# WiFi.net
KiCad netlist of a schematic drawn in Altium Designer
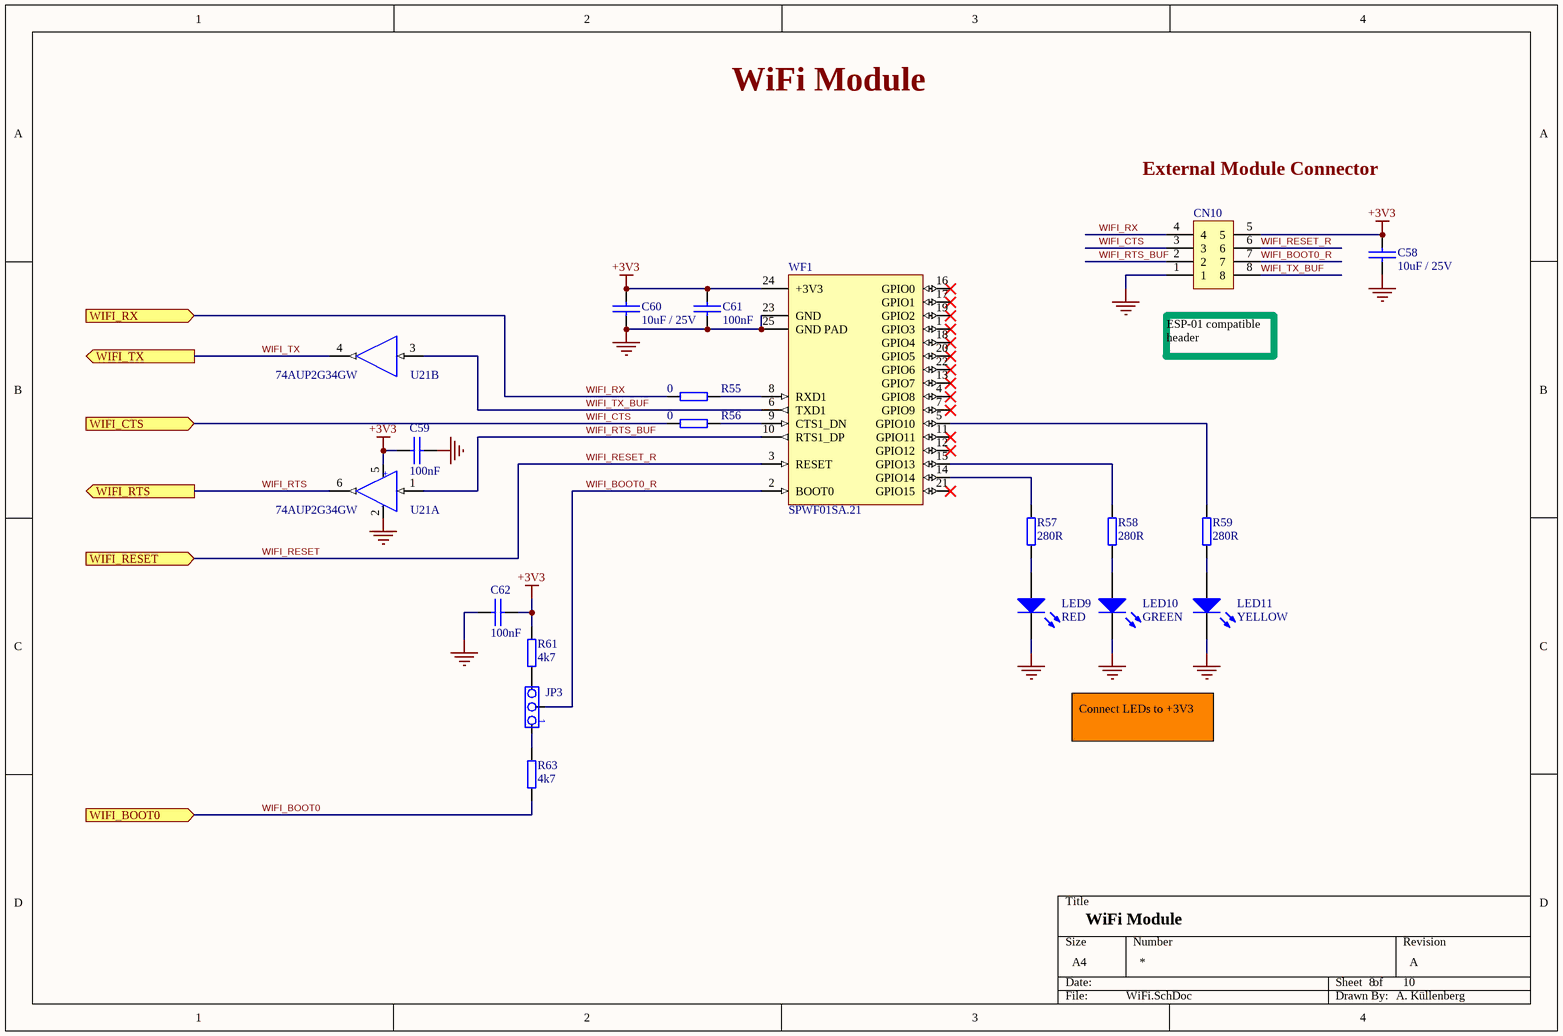
[diagram p0: WiFi.SchDoc]

(export (version "E")
  (design (tool "Eeschema 10.0.6"))
  (components
    (comp (ref "C58")
      (value "10uF / 25V")
      (footprint "C0603")
      (description "CAP CER 10UF 25V X5R 0603")
      (fields
        (field (name "PART NUMBER") "ZRB18AR61E106ME01L")
        (field (name "MANUFACTURER") "Murata Electronics North America")
      )
      (libsource (lib "AKLib") (part "CAP"))
    )
    (comp (ref "C59")
      (value "100nF")
      (footprint "C0603")
      (description "CAP CER 0.1UF 50V X7R 0603")
      (fields (field (name "PART NUMBER") "C0603C104K5RACTU") (field (name "MANUFACTURER") "Kemet"))
      (libsource (lib "AKLib") (part "CAP"))
    )
    (comp (ref "C60")
      (value "10uF / 25V")
      (footprint "C0603")
      (description "CAP CER 10UF 25V X5R 0603")
      (fields
        (field (name "PART NUMBER") "ZRB18AR61E106ME01L")
        (field (name "MANUFACTURER") "Murata Electronics North America")
      )
      (libsource (lib "AKLib") (part "CAP"))
    )
    (comp (ref "C61")
      (value "100nF")
      (footprint "C0603")
      (description "CAP CER 0.1UF 50V X7R 0603")
      (fields (field (name "PART NUMBER") "C0603C104K5RACTU") (field (name "MANUFACTURER") "Kemet"))
      (libsource (lib "AKLib") (part "CAP"))
    )
    (comp (ref "C62")
      (value "100nF")
      (footprint "C0603")
      (description "CAP CER 0.1UF 50V X7R 0603")
      (fields (field (name "PART NUMBER") "C0603C104K5RACTU") (field (name "MANUFACTURER") "Kemet"))
      (libsource (lib "AKLib") (part "CAP"))
    )
    (comp (ref "CN10")
      (value "HDR 2x4")
      (footprint "PPPC042LFBN-RC")
      (description "CONN HEADER FMAL 8PS .1\" DL GOLD")
      (fields
        (field (name "PART NUMBER") "PPPC042LFBN-RC")
        (field (name "MANUFACTURER") "Sullins Connector Solutions")
      )
      (libsource (lib "AKLib") (part "Header 2-4"))
    )
    (comp (ref "JP3")
      (value "JP")
      (footprint "HDR1x3")
      (description "CONN HEADER 3 POS 2.54")
      (fields
        (field (name "PART NUMBER") "61300311121")
        (field (name "MANUFACTURER") "Wurth Electronics Inc.")
      )
      (libsource (lib "AKLib") (part "JP1x3"))
    )
    (comp (ref "LED9")
      (value "RED")
      (footprint "LED_0603_RED")
      (description "LED RED CLEAR 0603 SMD")
      (fields (field (name "PART NUMBER") "LTST-C190KRKT") (field (name "MANUFACTURER") "Lite-On Inc."))
      (libsource (lib "AKLib") (part "LED"))
    )
    (comp (ref "LED10")
      (value "GREEN")
      (footprint "LED_0603_GREEN")
      (description "LED GREEN CLEAR 0603 SMD")
      (fields (field (name "PART NUMBER") "LTST-C190KGKT") (field (name "MANUFACTURER") "Lite-On Inc."))
      (libsource (lib "AKLib") (part "LED"))
    )
    (comp (ref "LED11")
      (value "YELLOW")
      (footprint "LED_0603_YELLOW")
      (description "LED YELLOW CLEAR 0603 SMD")
      (fields (field (name "PART NUMBER") "LTST-C190KSKT") (field (name "MANUFACTURER") "Lite-On Inc."))
      (libsource (lib "AKLib") (part "LED"))
    )
    (comp (ref "R55")
      (value "0")
      (footprint "R0603")
      (description "RES SMD 0.0OHM JUMPER 1/10W 0603")
      (fields (field (name "PART NUMBER") "RC0603JR-070RL") (field (name "MANUFACTURER") "Yageo"))
      (libsource (lib "AKLib") (part "RES"))
    )
    (comp (ref "R56")
      (value "0")
      (footprint "R0603")
      (description "RES SMD 0.0OHM JUMPER 1/10W 0603")
      (fields (field (name "PART NUMBER") "RC0603JR-070RL") (field (name "MANUFACTURER") "Yageo"))
      (libsource (lib "AKLib") (part "RES"))
    )
    (comp (ref "R57")
      (value "280R")
      (footprint "R0603")
      (description "RES SMD 280 OHM 1% 1/10W 0603")
      (fields (field (name "PART NUMBER") "RC0603FR-07280RL") (field (name "MANUFACTURER") "Yageo"))
      (libsource (lib "AKLib") (part "RES"))
    )
    (comp (ref "R58")
      (value "280R")
      (footprint "R0603")
      (description "RES SMD 280 OHM 1% 1/10W 0603")
      (fields (field (name "PART NUMBER") "RC0603FR-07280RL") (field (name "MANUFACTURER") "Yageo"))
      (libsource (lib "AKLib") (part "RES"))
    )
    (comp (ref "R59")
      (value "280R")
      (footprint "R0603")
      (description "RES SMD 280 OHM 1% 1/10W 0603")
      (fields (field (name "PART NUMBER") "RC0603FR-07280RL") (field (name "MANUFACTURER") "Yageo"))
      (libsource (lib "AKLib") (part "RES"))
    )
    (comp (ref "R61")
      (value "4k7")
      (footprint "R0603")
      (description "RES SMD 4.7K OHM 1% 1/10W 0603")
      (fields (field (name "PART NUMBER") "CRCW06034K70FKEA") (field (name "MANUFACTURER") "Vishay Dale"))
      (libsource (lib "AKLib") (part "RES"))
    )
    (comp (ref "R63")
      (value "4k7")
      (footprint "R0603")
      (description "RES SMD 4.7K OHM 1% 1/10W 0603")
      (fields (field (name "PART NUMBER") "CRCW06034K70FKEA") (field (name "MANUFACTURER") "Vishay Dale"))
      (libsource (lib "AKLib") (part "RES"))
    )
    (comp (ref "U21")
      (value "74AUP2G34GW")
      (footprint "SOT363")
      (description "IC BUFF DL LOW PWR N-INV 6TSSOP")
      (fields
        (field (name "PART NUMBER") "74AUP2G34GW,125")
        (field (name "MANUFACTURER") "Nexperia USA Inc.")
      )
      (libsource (lib "AKLib") (part "74AUP2G34GW"))
    )
    (comp (ref "WF1")
      (value "SPWF01SA.21")
      (footprint "SPWF01SA")
      (description "RF TXRX MODULE WIFI CHIP ANT")
      (fields (field (name "MANUFACTURER") "STMicroelectronics"))
      (libsource (lib "AKLib") (part "SPWF01Sx"))
    )
  )
  (nets
    (net (code "1") (name "+3V3") (class "Default")
      (node (ref "C58") (pin "2") (pinfunction "2_2") (pintype "passive"))
      (node (ref "C59") (pin "2") (pinfunction "2_2") (pintype "passive"))
      (node (ref "C60") (pin "2") (pinfunction "2_2") (pintype "passive"))
      (node (ref "C61") (pin "2") (pinfunction "2_2") (pintype "passive"))
      (node (ref "C62") (pin "1") (pinfunction "1_1") (pintype "passive"))
      (node (ref "CN10") (pin "5") (pinfunction "5_5") (pintype "passive"))
      (node (ref "R61") (pin "2") (pinfunction "2_2") (pintype "passive"))
      (node (ref "U21") (pin "5") (pinfunction "5_5") (pintype "passive"))
      (node (ref "WF1") (pin "24") (pinfunction "+3V3_24") (pintype "power_in"))
    )
    (net (code "2") (name "/WIFI_BOOT0") (class "Default")
      (node (ref "R63") (pin "1") (pinfunction "1_1") (pintype "passive"))
    )
    (net (code "3") (name "/WIFI_BOOT0_R") (class "Default")
      (node (ref "CN10") (pin "7") (pinfunction "7_7") (pintype "passive"))
      (node (ref "JP3") (pin "2") (pinfunction "2_2") (pintype "passive"))
      (node (ref "WF1") (pin "2") (pinfunction "BOOT0_2") (pintype "input"))
    )
    (net (code "4") (name "/WIFI_CTS") (class "Default")
      (node (ref "CN10") (pin "3") (pinfunction "3_3") (pintype "passive"))
      (node (ref "R56") (pin "1") (pinfunction "1_1") (pintype "passive"))
    )
    (net (code "5") (name "/WIFI_RESET") (class "Default")
      (node (ref "CN10") (pin "6") (pinfunction "6_6") (pintype "passive"))
      (node (ref "WF1") (pin "3") (pinfunction "RESET_3") (pintype "input"))
    )
    (net (code "6") (name "/WIFI_RTS") (class "Default")
      (node (ref "U21") (pin "6") (pinfunction "6_6") (pintype "output"))
    )
    (net (code "7") (name "/WIFI_RTS_BUF") (class "Default")
      (node (ref "CN10") (pin "2") (pinfunction "2_2") (pintype "passive"))
      (node (ref "U21") (pin "1") (pinfunction "1_1") (pintype "input"))
      (node (ref "WF1") (pin "10") (pinfunction "RTS1_DP_10") (pintype "output"))
    )
    (net (code "8") (name "/WIFI_RX") (class "Default")
      (node (ref "CN10") (pin "4") (pinfunction "4_4") (pintype "passive"))
      (node (ref "R55") (pin "1") (pinfunction "1_1") (pintype "passive"))
    )
    (net (code "9") (name "/WIFI_TX") (class "Default")
      (node (ref "U21") (pin "4") (pinfunction "4_4") (pintype "output"))
    )
    (net (code "10") (name "/WIFI_TX_BUF") (class "Default")
      (node (ref "CN10") (pin "8") (pinfunction "8_8") (pintype "passive"))
      (node (ref "U21") (pin "3") (pinfunction "3_3") (pintype "input"))
      (node (ref "WF1") (pin "6") (pinfunction "TXD1_6") (pintype "output"))
    )
    (net (code "11") (name "GND") (class "Default")
      (node (ref "C58") (pin "1") (pinfunction "1_1") (pintype "passive"))
      (node (ref "C59") (pin "1") (pinfunction "1_1") (pintype "passive"))
      (node (ref "C60") (pin "1") (pinfunction "1_1") (pintype "passive"))
      (node (ref "C61") (pin "1") (pinfunction "1_1") (pintype "passive"))
      (node (ref "C62") (pin "2") (pinfunction "2_2") (pintype "passive"))
      (node (ref "CN10") (pin "1") (pinfunction "1_1") (pintype "passive"))
      (node (ref "LED10") (pin "2") (pinfunction "K_2") (pintype "passive"))
      (node (ref "LED11") (pin "2") (pinfunction "K_2") (pintype "passive"))
      (node (ref "LED9") (pin "2") (pinfunction "K_2") (pintype "passive"))
      (node (ref "U21") (pin "2") (pinfunction "2_2") (pintype "power_in"))
      (node (ref "WF1") (pin "23") (pinfunction "GND_23") (pintype "power_in"))
      (node (ref "WF1") (pin "25") (pinfunction "GND_PAD_25") (pintype "power_in"))
    )
    (net (code "12") (name "Net-(JP3-Pad1)") (class "Default")
      (node (ref "JP3") (pin "1") (pinfunction "1_1") (pintype "passive"))
      (node (ref "R63") (pin "2") (pinfunction "2_2") (pintype "passive"))
    )
    (net (code "13") (name "Net-(JP3-Pad3)") (class "Default")
      (node (ref "JP3") (pin "3") (pinfunction "3_3") (pintype "passive"))
      (node (ref "R61") (pin "1") (pinfunction "1_1") (pintype "passive"))
    )
    (net (code "14") (name "Net-(LED9-A)") (class "Default")
      (node (ref "LED9") (pin "1") (pinfunction "A_1") (pintype "passive"))
      (node (ref "R57") (pin "1") (pinfunction "1_1") (pintype "passive"))
    )
    (net (code "15") (name "Net-(LED10-A)") (class "Default")
      (node (ref "LED10") (pin "1") (pinfunction "A_1") (pintype "passive"))
      (node (ref "R58") (pin "1") (pinfunction "1_1") (pintype "passive"))
    )
    (net (code "16") (name "Net-(LED11-A)") (class "Default")
      (node (ref "LED11") (pin "1") (pinfunction "A_1") (pintype "passive"))
      (node (ref "R59") (pin "1") (pinfunction "1_1") (pintype "passive"))
    )
    (net (code "17") (name "Net-(WF1-CTS1_DN)") (class "Default")
      (node (ref "R56") (pin "2") (pinfunction "2_2") (pintype "passive"))
      (node (ref "WF1") (pin "9") (pinfunction "CTS1_DN_9") (pintype "input"))
    )
    (net (code "18") (name "Net-(WF1-GPIO10)") (class "Default")
      (node (ref "R59") (pin "2") (pinfunction "2_2") (pintype "passive"))
      (node (ref "WF1") (pin "5") (pinfunction "GPIO10_5") (pintype "bidirectional"))
    )
    (net (code "19") (name "Net-(WF1-GPIO13)") (class "Default")
      (node (ref "R58") (pin "2") (pinfunction "2_2") (pintype "passive"))
      (node (ref "WF1") (pin "15") (pinfunction "GPIO13_15") (pintype "bidirectional"))
    )
    (net (code "20") (name "Net-(WF1-GPIO14)") (class "Default")
      (node (ref "R57") (pin "2") (pinfunction "2_2") (pintype "passive"))
      (node (ref "WF1") (pin "14") (pinfunction "GPIO14_14") (pintype "bidirectional"))
    )
    (net (code "21") (name "Net-(WF1-RXD1)") (class "Default")
      (node (ref "R55") (pin "2") (pinfunction "2_2") (pintype "passive"))
      (node (ref "WF1") (pin "8") (pinfunction "RXD1_8") (pintype "input"))
    )
    (net (code "22") (name "unconnected-(WF1-GPIO0-Pad16)") (class "Default")
      (node (ref "WF1") (pin "16") (pinfunction "GPIO0_16") (pintype "bidirectional+no_connect"))
    )
    (net (code "23") (name "unconnected-(WF1-GPIO1-Pad17)") (class "Default")
      (node (ref "WF1") (pin "17") (pinfunction "GPIO1_17") (pintype "bidirectional+no_connect"))
    )
    (net (code "24") (name "unconnected-(WF1-GPIO2-Pad19)") (class "Default")
      (node (ref "WF1") (pin "19") (pinfunction "GPIO2_19") (pintype "bidirectional+no_connect"))
    )
    (net (code "25") (name "unconnected-(WF1-GPIO3-Pad1)") (class "Default")
      (node (ref "WF1") (pin "1") (pinfunction "GPIO3_1") (pintype "bidirectional+no_connect"))
    )
    (net (code "26") (name "unconnected-(WF1-GPIO4-Pad18)") (class "Default")
      (node (ref "WF1") (pin "18") (pinfunction "GPIO4_18") (pintype "bidirectional+no_connect"))
    )
    (net (code "27") (name "unconnected-(WF1-GPIO5-Pad20)") (class "Default")
      (node (ref "WF1") (pin "20") (pinfunction "GPIO5_20") (pintype "bidirectional+no_connect"))
    )
    (net (code "28") (name "unconnected-(WF1-GPIO6-Pad22)") (class "Default")
      (node (ref "WF1") (pin "22") (pinfunction "GPIO6_22") (pintype "bidirectional+no_connect"))
    )
    (net (code "29") (name "unconnected-(WF1-GPIO7-Pad13)") (class "Default")
      (node (ref "WF1") (pin "13") (pinfunction "GPIO7_13") (pintype "bidirectional+no_connect"))
    )
    (net (code "30") (name "unconnected-(WF1-GPIO8-Pad4)") (class "Default")
      (node (ref "WF1") (pin "4") (pinfunction "GPIO8_4") (pintype "bidirectional+no_connect"))
    )
    (net (code "31") (name "unconnected-(WF1-GPIO9-Pad7)") (class "Default")
      (node (ref "WF1") (pin "7") (pinfunction "GPIO9_7") (pintype "bidirectional+no_connect"))
    )
    (net (code "32") (name "unconnected-(WF1-GPIO11-Pad11)") (class "Default")
      (node (ref "WF1") (pin "11") (pinfunction "GPIO11_11") (pintype "bidirectional+no_connect"))
    )
    (net (code "33") (name "unconnected-(WF1-GPIO12-Pad12)") (class "Default")
      (node (ref "WF1") (pin "12") (pinfunction "GPIO12_12") (pintype "bidirectional+no_connect"))
    )
    (net (code "34") (name "unconnected-(WF1-GPIO15-Pad21)") (class "Default")
      (node (ref "WF1") (pin "21") (pinfunction "GPIO15_21") (pintype "bidirectional+no_connect"))
    )
  )
)
